# Heat_Sensing_Device.net
KiCad netlist of a schematic drawn in EAGLE
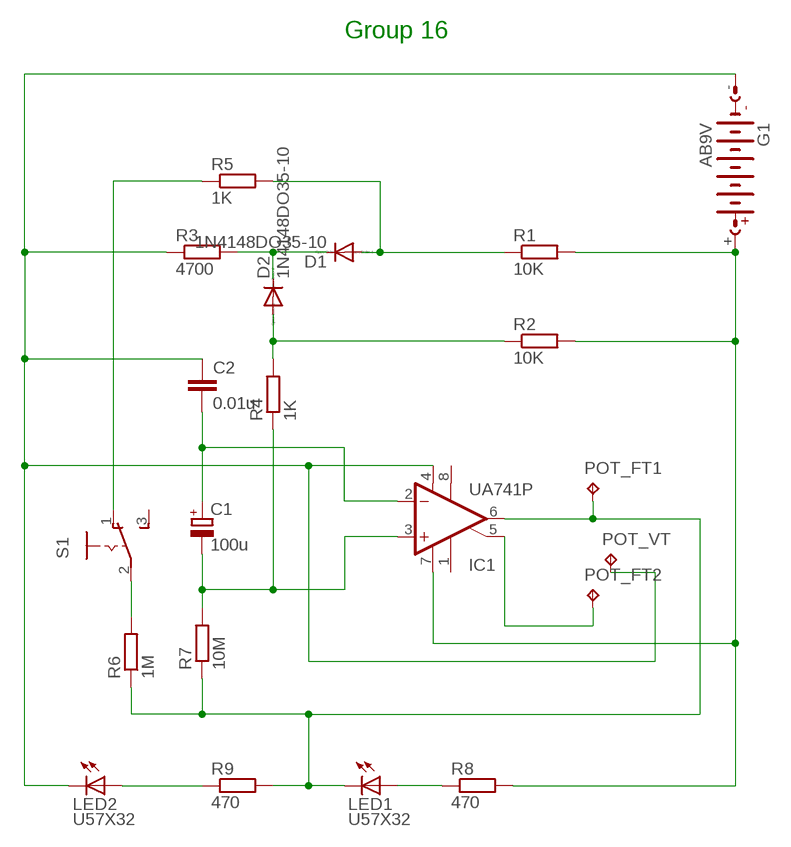
[diagram p0: schematic, sheet 1]

(export (version "E")
  (design (tool "Eeschema 10.0.6"))
  (components
    (comp (ref "C1")
      (value "100u")
      (footprint "eagle-import:E5-10,5")
      (libsource (lib "eagle-import") (part "CPOL-EUE5-10.5"))
    )
    (comp (ref "C2")
      (value "0.01u")
      (footprint "eagle-import:C025-050X050")
      (libsource (lib "eagle-import") (part "C-EU025-050X050"))
    )
    (comp (ref "D1")
      (value "1N4148DO35-10")
      (footprint "eagle-import:DO35-10")
      (libsource (lib "eagle-import") (part "1N4148DO35-10"))
    )
    (comp (ref "D2")
      (value "1N4148DO35-10")
      (footprint "eagle-import:DO35-10")
      (libsource (lib "eagle-import") (part "1N4148DO35-10"))
    )
    (comp (ref "G1")
      (value "AB9V")
      (footprint "eagle-import:AB9V")
      (libsource (lib "eagle-import") (part "AB9V"))
    )
    (comp (ref "IC1")
      (value "UA741P")
      (footprint "eagle-import:DIL08")
      (libsource (lib "eagle-import") (part "741PUA"))
    )
    (comp (ref "LED1")
      (value "U57X32")
      (footprint "eagle-import:U57X32")
      (libsource (lib "eagle-import") (part "U57X32"))
    )
    (comp (ref "LED2")
      (value "U57X32")
      (footprint "eagle-import:U57X32")
      (libsource (lib "eagle-import") (part "U57X32"))
    )
    (comp (ref "POT_FT1")
      (value "TPPAD1-17")
      (footprint "eagle-import:P1-17")
      (libsource (lib "eagle-import") (part "TPPAD1-17"))
    )
    (comp (ref "POT_FT2")
      (value "TPPAD1-17")
      (footprint "eagle-import:P1-17")
      (libsource (lib "eagle-import") (part "TPPAD1-17"))
    )
    (comp (ref "POT_VT")
      (value "TPPAD1-17")
      (footprint "eagle-import:P1-17")
      (libsource (lib "eagle-import") (part "TPPAD1-17"))
    )
    (comp (ref "R1")
      (value "10K")
      (footprint "eagle-import:0204_5")
      (libsource (lib "eagle-import") (part "R-EU_0204/5"))
    )
    (comp (ref "R2")
      (value "10K")
      (footprint "eagle-import:0204_5")
      (libsource (lib "eagle-import") (part "R-EU_0204/5"))
    )
    (comp (ref "R3")
      (value "4700")
      (footprint "eagle-import:0204_5")
      (libsource (lib "eagle-import") (part "R-EU_0204/5"))
    )
    (comp (ref "R4")
      (value "1K")
      (footprint "eagle-import:0204_5")
      (libsource (lib "eagle-import") (part "R-EU_0204/5"))
    )
    (comp (ref "R5")
      (value "1K")
      (footprint "eagle-import:0204_5")
      (libsource (lib "eagle-import") (part "R-EU_0204/5"))
    )
    (comp (ref "R6")
      (value "1M")
      (footprint "eagle-import:0204_5")
      (libsource (lib "eagle-import") (part "R-EU_0204/5"))
    )
    (comp (ref "R7")
      (value "10M")
      (footprint "eagle-import:0204_5")
      (libsource (lib "eagle-import") (part "R-EU_0204/5"))
    )
    (comp (ref "R8")
      (value "470")
      (footprint "eagle-import:0204_5")
      (libsource (lib "eagle-import") (part "R-EU_0204/5"))
    )
    (comp (ref "R9")
      (value "470")
      (footprint "eagle-import:0204_5")
      (libsource (lib "eagle-import") (part "R-EU_0204/5"))
    )
    (comp (ref "S1")
      (value "255SB")
      (footprint "eagle-import:255SB")
      (libsource (lib "eagle-import") (part "255SB"))
    )
  )
  (nets
    (net (code "1") (name "Net-(D1-PadA)") (class "Default")
      (node (ref "D1") (pin "A") (pinfunction "A_A") (pintype "passive"))
      (node (ref "R1") (pin "1") (pinfunction "1_1") (pintype "passive"))
      (node (ref "R5") (pin "2") (pinfunction "2_2") (pintype "passive"))
    )
    (net (code "2") (name "Net-(D1-PadC)") (class "Default")
      (node (ref "D1") (pin "C") (pinfunction "C_C") (pintype "passive"))
      (node (ref "D2") (pin "C") (pinfunction "C_C") (pintype "passive"))
      (node (ref "R3") (pin "2") (pinfunction "2_2") (pintype "passive"))
    )
    (net (code "3") (name "Net-(D2-PadA)") (class "Default")
      (node (ref "D2") (pin "A") (pinfunction "A_A") (pintype "passive"))
      (node (ref "R2") (pin "1") (pinfunction "1_1") (pintype "passive"))
      (node (ref "R4") (pin "2") (pinfunction "2_2") (pintype "passive"))
    )
    (net (code "4") (name "Net-(IC1-+IN)") (class "Default")
      (node (ref "C1") (pin "-") (pinfunction "-_-") (pintype "passive"))
      (node (ref "IC1") (pin "3") (pinfunction "+IN_3") (pintype "input"))
      (node (ref "R4") (pin "1") (pinfunction "1_1") (pintype "passive"))
      (node (ref "R7") (pin "2") (pinfunction "2_2") (pintype "passive"))
    )
    (net (code "5") (name "Net-(IC1--IN)") (class "Default")
      (node (ref "C1") (pin "+") (pinfunction "+_+") (pintype "passive"))
      (node (ref "C2") (pin "2") (pinfunction "2_2") (pintype "passive"))
      (node (ref "IC1") (pin "2") (pinfunction "-IN_2") (pintype "input"))
    )
    (net (code "6") (name "Net-(IC1-ON2)") (class "Default")
      (node (ref "IC1") (pin "5") (pinfunction "ON2_5") (pintype "passive"))
      (node (ref "POT_FT2") (pin "TP") (pinfunction "TP_TP") (pintype "input"))
    )
    (net (code "7") (name "Net-(IC1-OUT)") (class "Default")
      (node (ref "IC1") (pin "6") (pinfunction "OUT_6") (pintype "output"))
      (node (ref "LED1") (pin "K") (pinfunction "C_K") (pintype "passive"))
      (node (ref "POT_FT1") (pin "TP") (pinfunction "TP_TP") (pintype "input"))
      (node (ref "R6") (pin "1") (pinfunction "1_1") (pintype "passive"))
      (node (ref "R7") (pin "1") (pinfunction "1_1") (pintype "passive"))
      (node (ref "R9") (pin "2") (pinfunction "2_2") (pintype "passive"))
    )
    (net (code "8") (name "Net-(IC1-V+)") (class "Default")
      (node (ref "G1") (pin "+") (pinfunction "+_+") (pintype "passive"))
      (node (ref "IC1") (pin "7") (pinfunction "V+_7") (pintype "power_in"))
      (node (ref "R1") (pin "2") (pinfunction "2_2") (pintype "passive"))
      (node (ref "R2") (pin "2") (pinfunction "2_2") (pintype "passive"))
      (node (ref "R8") (pin "2") (pinfunction "2_2") (pintype "passive"))
    )
    (net (code "9") (name "Net-(IC1-V-)") (class "Default")
      (node (ref "C2") (pin "1") (pinfunction "1_1") (pintype "passive"))
      (node (ref "G1") (pin "-") (pinfunction "-_-") (pintype "passive"))
      (node (ref "IC1") (pin "4") (pinfunction "V-_4") (pintype "power_in"))
      (node (ref "LED2") (pin "K") (pinfunction "C_K") (pintype "passive"))
      (node (ref "POT_VT") (pin "TP") (pinfunction "TP_TP") (pintype "input"))
      (node (ref "R3") (pin "1") (pinfunction "1_1") (pintype "passive"))
    )
    (net (code "10") (name "Net-(LED1-PadA)") (class "Default")
      (node (ref "LED1") (pin "A") (pinfunction "A_A") (pintype "passive"))
      (node (ref "R8") (pin "1") (pinfunction "1_1") (pintype "passive"))
    )
    (net (code "11") (name "Net-(LED2-PadA)") (class "Default")
      (node (ref "LED2") (pin "A") (pinfunction "A_A") (pintype "passive"))
      (node (ref "R9") (pin "1") (pinfunction "1_1") (pintype "passive"))
    )
    (net (code "12") (name "Net-(S1-O)") (class "Default")
      (node (ref "R5") (pin "1") (pinfunction "1_1") (pintype "passive"))
      (node (ref "S1") (pin "1") (pinfunction "O_1") (pintype "passive"))
    )
    (net (code "13") (name "Net-(S1-P)") (class "Default")
      (node (ref "R6") (pin "2") (pinfunction "2_2") (pintype "passive"))
      (node (ref "S1") (pin "2") (pinfunction "P_2") (pintype "passive"))
    )
    (net (code "14") (name "unconnected-(IC1-ON1-Pad1)") (class "Default")
      (node (ref "IC1") (pin "1") (pinfunction "ON1_1") (pintype "passive"))
    )
    (net (code "15") (name "unconnected-(IC1-OPT-Pad8)") (class "Default")
      (node (ref "IC1") (pin "8") (pinfunction "OPT_8") (pintype "passive"))
    )
    (net (code "16") (name "unconnected-(S1-S-Pad3)") (class "Default")
      (node (ref "S1") (pin "3") (pinfunction "S_3") (pintype "passive"))
    )
  )
)
